# Wall_Power.net
KiCad netlist of a schematic drawn in Altium Designer
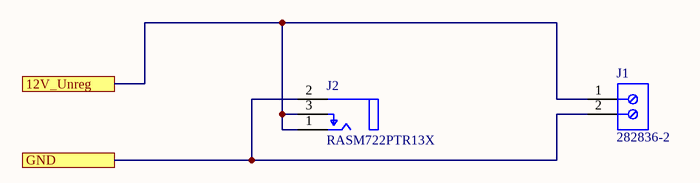
[diagram p0: Wall_Power.SchDoc]

(export (version "E")
  (design (tool "Eeschema 10.0.6"))
  (components
    (comp (ref "J1")
      (value "282836-2")
      (footprint "TECO-282836-2_V")
      (description "Female Header, Pitch 5 mm, 1 x 2 Position, Height 10 mm, Tail Length 3.5 mm, Rohs, Bulk")
      (fields (field (name "VOLTAGE") "300V") (field (name "MANUFACTURER") "TE Connectivity"))
      (libsource (lib "Altium Content Vault") (part "CN-1P-F-TB2"))
    )
    (comp (ref "J2")
      (value "RASM722PTR13X")
      (footprint "FP-RASM722PTR13X-MFG")
      (description "CONN PWR JACK 2.1X5.5MM SOLDER")
      (libsource (lib "Altium Content Vault") (part "69023cd999ddc70d2a190894d9bbb58"))
    )
  )
  (nets
    (net (code "1") (name "/12V_Unreg") (class "Default")
      (node (ref "J1") (pin "1") (pinfunction "1_1") (pintype "passive"))
      (node (ref "J2") (pin "1") (pinfunction "TIP_TERMINAL(CENTER_PIN)_1") (pintype "passive"))
      (node (ref "J2") (pin "3") (pinfunction "SHUNT_TERMINAL_3") (pintype "passive"))
    )
    (net (code "2") (name "/GND") (class "Default")
      (node (ref "J1") (pin "2") (pinfunction "2_2") (pintype "passive"))
      (node (ref "J2") (pin "2") (pinfunction "SLEEVE_TERMINAL_2") (pintype "passive"))
    )
  )
)
